# obc-v2_EXP-CAN-RS422.net
KiCad netlist of a schematic drawn in Altium Designer
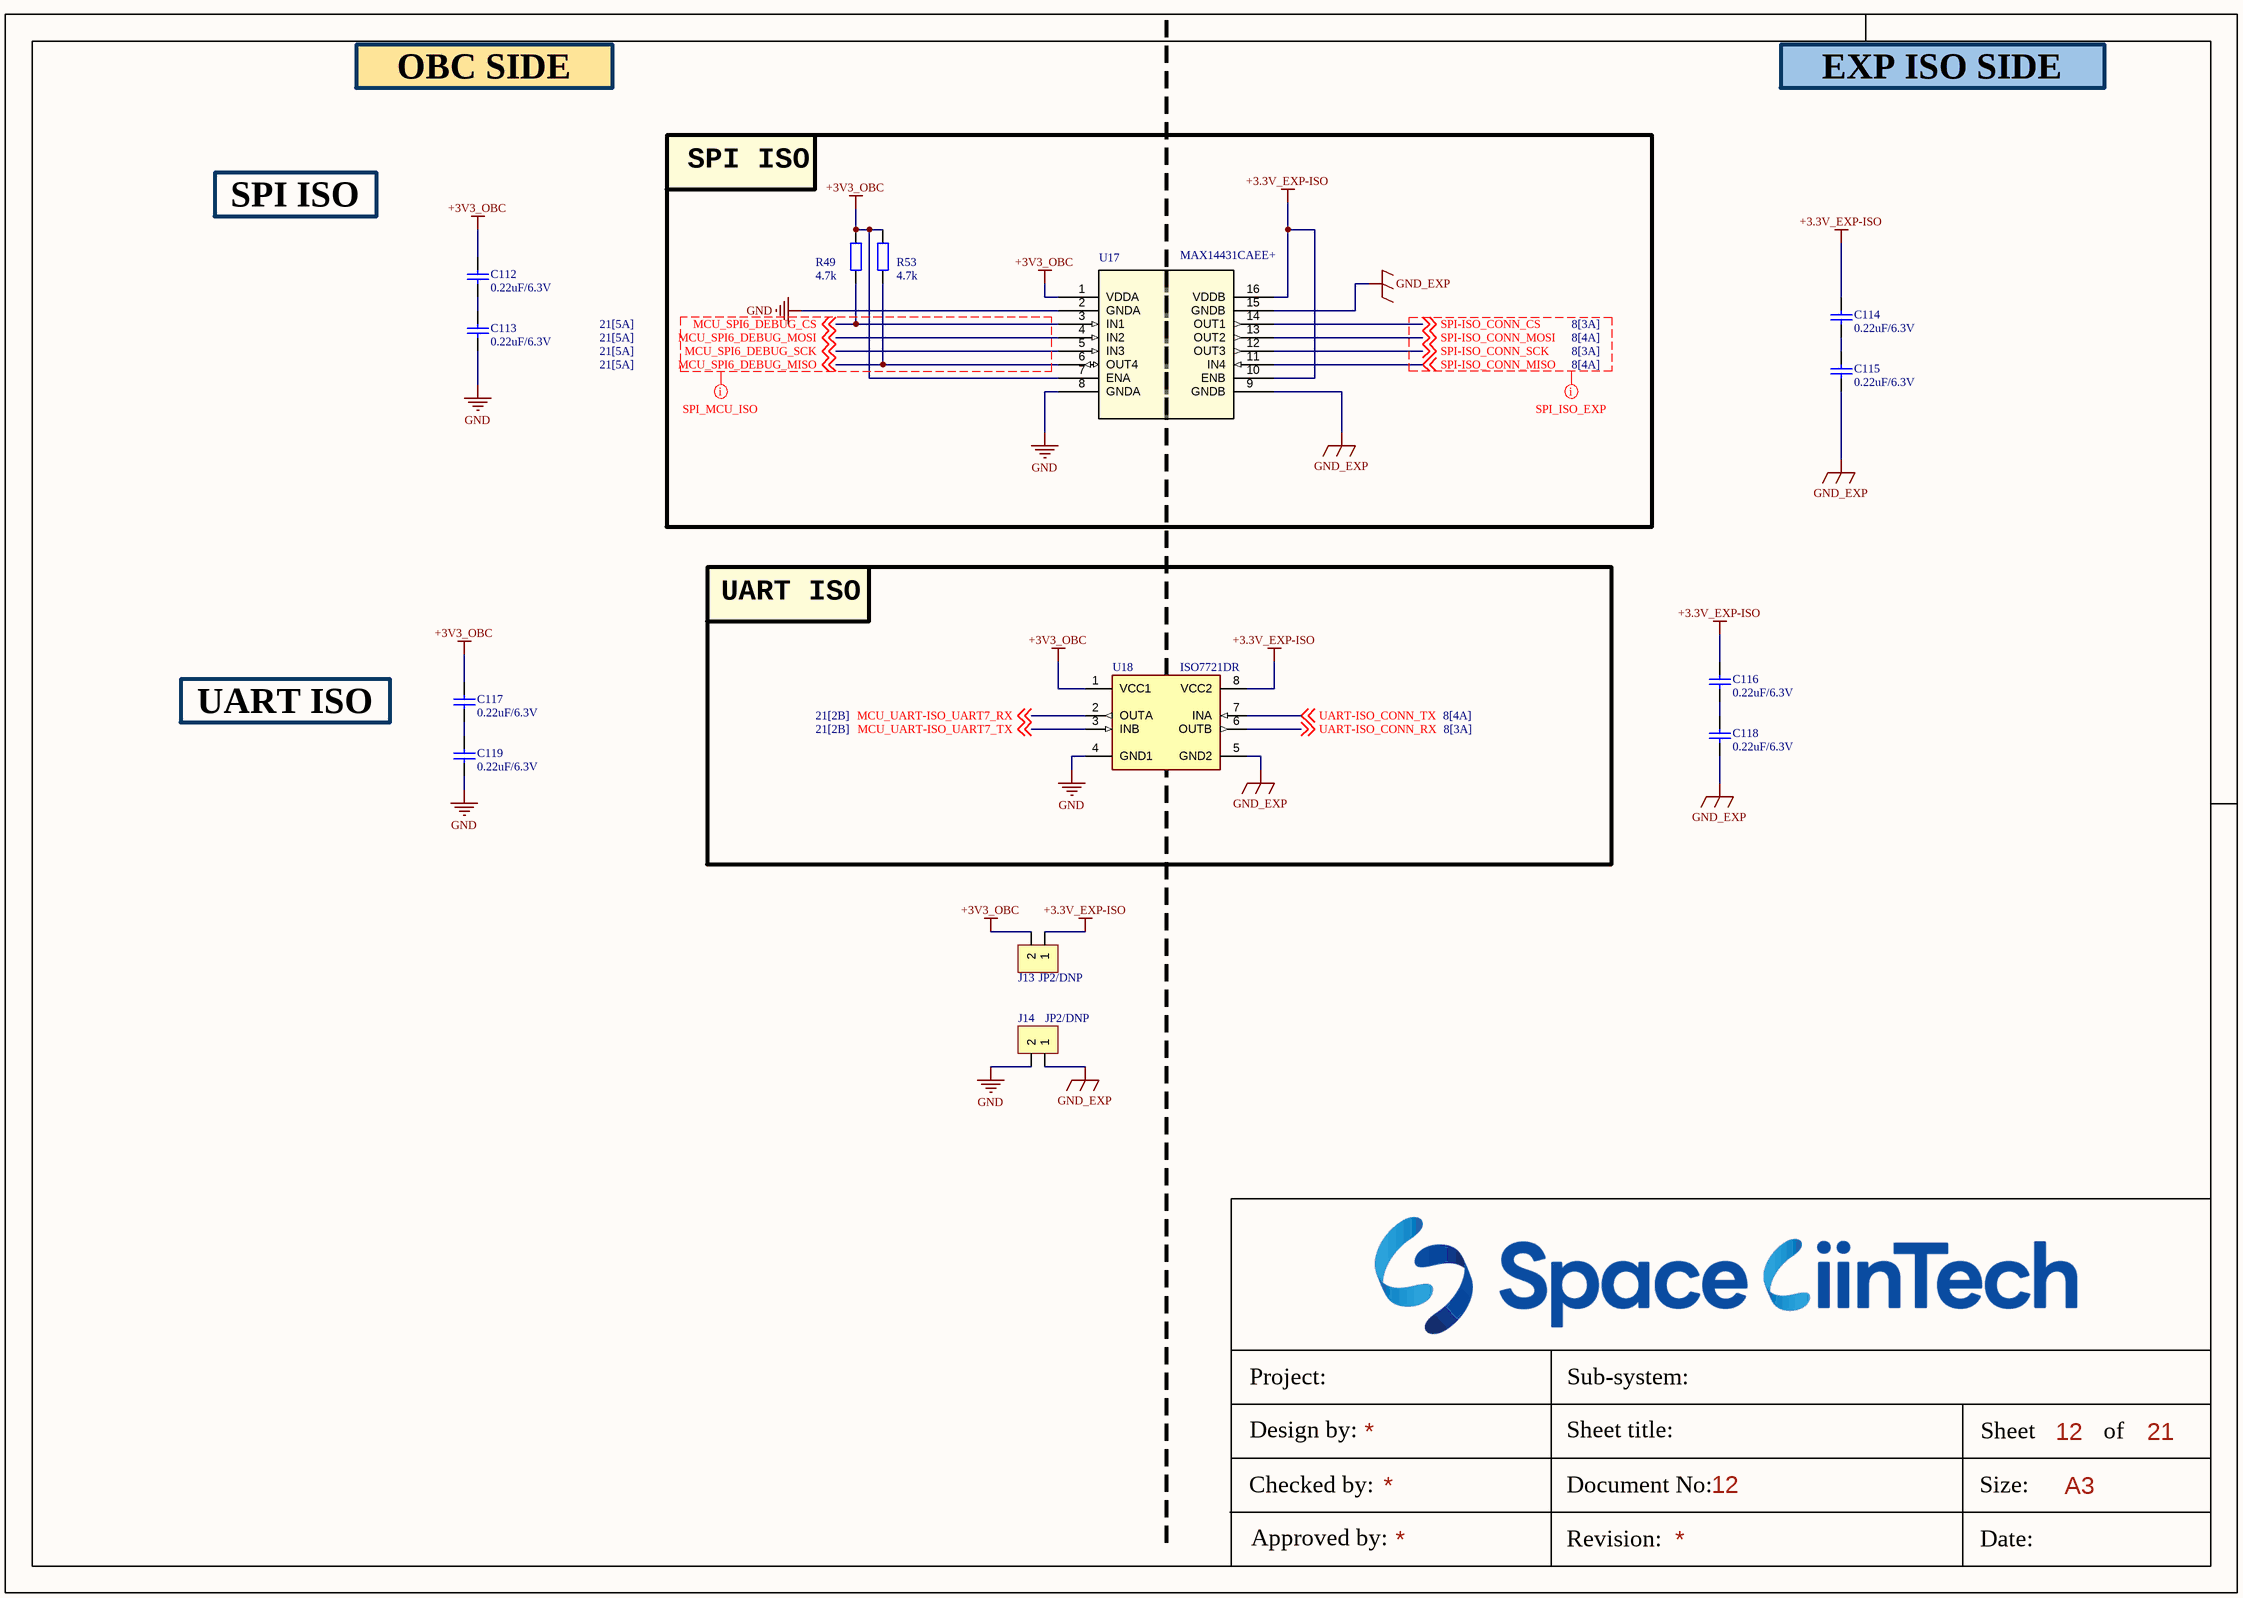
[diagram p0: obc-v2_EXP-CAN-RS422.SchDoc]

(export (version "E")
  (design (tool "Eeschema 10.0.6"))
  (components
    (comp (ref "C112")
      (value "0.22uF/6.3V")
      (footprint "CAP_C_1005X60")
      (description "CAPC")
      (libsource (lib "Altium_Lib_by_KhueNguyenCreator") (part "Tu 0402 33nF 10V"))
    )
    (comp (ref "C113")
      (value "0.22uF/6.3V")
      (footprint "CAP_C_1005X60")
      (description "CAPC")
      (libsource (lib "Altium_Lib_by_KhueNguyenCreator") (part "Tu 0402 33nF 10V"))
    )
    (comp (ref "C114")
      (value "0.22uF/6.3V")
      (footprint "CAP_C_1005X60")
      (description "CAPC")
      (libsource (lib "Altium_Lib_by_KhueNguyenCreator") (part "Tu 0402 33nF 10V"))
    )
    (comp (ref "C115")
      (value "0.22uF/6.3V")
      (footprint "CAP_C_1005X60")
      (description "CAPC")
      (libsource (lib "Altium_Lib_by_KhueNguyenCreator") (part "Tu 0402 33nF 10V"))
    )
    (comp (ref "C116")
      (value "0.22uF/6.3V")
      (footprint "CAP_C_1005X60")
      (description "CAPC")
      (libsource (lib "Altium_Lib_by_KhueNguyenCreator") (part "Tu 0402 33nF 10V"))
    )
    (comp (ref "C117")
      (value "0.22uF/6.3V")
      (footprint "CAP_C_1005X60")
      (description "CAPC")
      (libsource (lib "Altium_Lib_by_KhueNguyenCreator") (part "Tu 0402 33nF 10V"))
    )
    (comp (ref "C118")
      (value "0.22uF/6.3V")
      (footprint "CAP_C_1005X60")
      (description "CAPC")
      (libsource (lib "Altium_Lib_by_KhueNguyenCreator") (part "Tu 0402 33nF 10V"))
    )
    (comp (ref "C119")
      (value "0.22uF/6.3V")
      (footprint "CAP_C_1005X60")
      (description "CAPC")
      (libsource (lib "Altium_Lib_by_KhueNguyenCreator") (part "Tu 0402 33nF 10V"))
    )
    (comp (ref "J13")
      (value "JP2/DNP")
      (footprint "JP2-D1T")
      (description "WR-PHD 2.54 mm Angled Socket Header")
      (fields
        (field (name "MANUFACTURER") "Würth Elektronik eiSos GmbH")
        (field (name "PARTNO") "613002143121")
        (field (name "CREATED BY") "Karrer Zheng")
      )
      (libsource (lib "") (part "JP2_1"))
    )
    (comp (ref "J14")
      (value "JP2/DNP")
      (footprint "JP2-D1T")
      (description "WR-PHD 2.54 mm Angled Socket Header")
      (fields
        (field (name "MANUFACTURER") "Würth Elektronik eiSos GmbH")
        (field (name "PARTNO") "613002143121")
        (field (name "CREATED BY") "Karrer Zheng")
      )
      (libsource (lib "TechMT.VN_Lib") (part "JP2"))
    )
    (comp (ref "R49")
      (value "4.7k")
      (footprint "RES_C_1608X60")
      (description "RES")
      (libsource (lib "Altium_Lib_by_KhueNguyenCreator") (part "Tro 0603 1% 10k"))
    )
    (comp (ref "R53")
      (value "4.7k")
      (footprint "RES_C_1608X60")
      (description "RES")
      (libsource (lib "Altium_Lib_by_KhueNguyenCreator") (part "Tro 0603 1% 10k"))
    )
    (comp (ref "U17")
      (value "MAX14431CAEE+")
      (footprint "21-0055Q_E16MS+1F_MXM")
      (description "No Description Available")
      (libsource (lib "MAX14431CAEE&plus_") (part "MAX14431CAEE+"))
    )
    (comp (ref "U18")
      (value "ISO7721DR")
      (footprint "SOIC127P602X173-8N")
      (description "Robust EMC, dual-channel, 1/1, reinforced digital isolator 8-SOIC -55 to 125")
      (libsource (lib "ISO7721DR") (part "ISO7721DR"))
    )
  )
  (nets
    (net (code "1") (name "+3.3V_EXP-ISO") (class "Default")
      (node (ref "C114") (pin "2") (pinfunction "2_2") (pintype "passive"))
      (node (ref "C116") (pin "2") (pinfunction "2_2") (pintype "passive"))
      (node (ref "J13") (pin "1") (pinfunction "1_1") (pintype "passive"))
      (node (ref "U17") (pin "10") (pinfunction "ENB_10") (pintype "passive"))
      (node (ref "U17") (pin "16") (pinfunction "VDDB_16") (pintype "power_in"))
      (node (ref "U18") (pin "8") (pinfunction "VCC2_8") (pintype "power_in"))
    )
    (net (code "2") (name "+3V3_OBC") (class "Default")
      (node (ref "C112") (pin "1") (pinfunction "1_1") (pintype "passive"))
      (node (ref "C117") (pin "1") (pinfunction "1_1") (pintype "passive"))
      (node (ref "J13") (pin "2") (pinfunction "2_2") (pintype "passive"))
      (node (ref "R49") (pin "2") (pinfunction "2_2") (pintype "passive"))
      (node (ref "R53") (pin "2") (pinfunction "2_2") (pintype "passive"))
      (node (ref "U17") (pin "1") (pinfunction "VDDA_1") (pintype "power_in"))
      (node (ref "U17") (pin "7") (pinfunction "ENA_7") (pintype "passive"))
      (node (ref "U18") (pin "1") (pinfunction "VCC1_1") (pintype "power_in"))
    )
    (net (code "3") (name "GND") (class "Default")
      (node (ref "C113") (pin "2") (pinfunction "2_2") (pintype "passive"))
      (node (ref "C119") (pin "2") (pinfunction "2_2") (pintype "passive"))
      (node (ref "J14") (pin "2") (pinfunction "2_2") (pintype "passive"))
      (node (ref "U17") (pin "2") (pinfunction "GNDA_2") (pintype "power_in"))
      (node (ref "U17") (pin "8") (pinfunction "GNDA_8") (pintype "power_in"))
      (node (ref "U18") (pin "4") (pinfunction "GND1_4") (pintype "power_in"))
    )
    (net (code "4") (name "GND_EXP") (class "Default")
      (node (ref "C115") (pin "1") (pinfunction "1_1") (pintype "passive"))
      (node (ref "C118") (pin "1") (pinfunction "1_1") (pintype "passive"))
      (node (ref "J14") (pin "1") (pinfunction "1_1") (pintype "passive"))
      (node (ref "U17") (pin "15") (pinfunction "GNDB_15") (pintype "power_in"))
      (node (ref "U17") (pin "9") (pinfunction "GNDB_9") (pintype "power_in"))
      (node (ref "U18") (pin "5") (pinfunction "GND2_5") (pintype "power_in"))
    )
    (net (code "5") (name "MCU_SPI6_DEBUG_CS") (class "Default")
      (node (ref "R49") (pin "1") (pinfunction "1_1") (pintype "passive"))
      (node (ref "U17") (pin "3") (pinfunction "IN1_3") (pintype "input"))
    )
    (net (code "6") (name "MCU_SPI6_DEBUG_MISO") (class "Default")
      (node (ref "R53") (pin "1") (pinfunction "1_1") (pintype "passive"))
      (node (ref "U17") (pin "6") (pinfunction "OUT4_6") (pintype "bidirectional"))
    )
    (net (code "7") (name "MCU_SPI6_DEBUG_MOSI") (class "Default")
      (node (ref "U17") (pin "4") (pinfunction "IN2_4") (pintype "input"))
    )
    (net (code "8") (name "MCU_SPI6_DEBUG_SCK") (class "Default")
      (node (ref "U17") (pin "5") (pinfunction "IN3_5") (pintype "input"))
    )
    (net (code "9") (name "MCU_UART-ISO_UART7_RX") (class "Default")
      (node (ref "U18") (pin "2") (pinfunction "OUTA_2") (pintype "output"))
    )
    (net (code "10") (name "MCU_UART-ISO_UART7_TX") (class "Default")
      (node (ref "U18") (pin "3") (pinfunction "INB_3") (pintype "input"))
    )
    (net (code "11") (name "Net-(C112-Pad2)") (class "Default")
      (node (ref "C112") (pin "2") (pinfunction "2_2") (pintype "passive"))
      (node (ref "C113") (pin "1") (pinfunction "1_1") (pintype "passive"))
    )
    (net (code "12") (name "Net-(C114-Pad1)") (class "Default")
      (node (ref "C114") (pin "1") (pinfunction "1_1") (pintype "passive"))
      (node (ref "C115") (pin "2") (pinfunction "2_2") (pintype "passive"))
    )
    (net (code "13") (name "Net-(C116-Pad1)") (class "Default")
      (node (ref "C116") (pin "1") (pinfunction "1_1") (pintype "passive"))
      (node (ref "C118") (pin "2") (pinfunction "2_2") (pintype "passive"))
    )
    (net (code "14") (name "Net-(C117-Pad2)") (class "Default")
      (node (ref "C117") (pin "2") (pinfunction "2_2") (pintype "passive"))
      (node (ref "C119") (pin "1") (pinfunction "1_1") (pintype "passive"))
    )
    (net (code "15") (name "SPI-ISO_CONN_CS") (class "Default")
      (node (ref "U17") (pin "14") (pinfunction "OUT1_14") (pintype "output"))
    )
    (net (code "16") (name "SPI-ISO_CONN_MISO") (class "Default")
      (node (ref "U17") (pin "11") (pinfunction "IN4_11") (pintype "input"))
    )
    (net (code "17") (name "SPI-ISO_CONN_MOSI") (class "Default")
      (node (ref "U17") (pin "13") (pinfunction "OUT2_13") (pintype "output"))
    )
    (net (code "18") (name "SPI-ISO_CONN_SCK") (class "Default")
      (node (ref "U17") (pin "12") (pinfunction "OUT3_12") (pintype "output"))
    )
    (net (code "19") (name "UART-ISO_CONN_RX") (class "Default")
      (node (ref "U18") (pin "6") (pinfunction "OUTB_6") (pintype "output"))
    )
    (net (code "20") (name "UART-ISO_CONN_TX") (class "Default")
      (node (ref "U18") (pin "7") (pinfunction "INA_7") (pintype "input"))
    )
  )
)
